# Opto.net
KiCad netlist of a schematic drawn in EAGLE
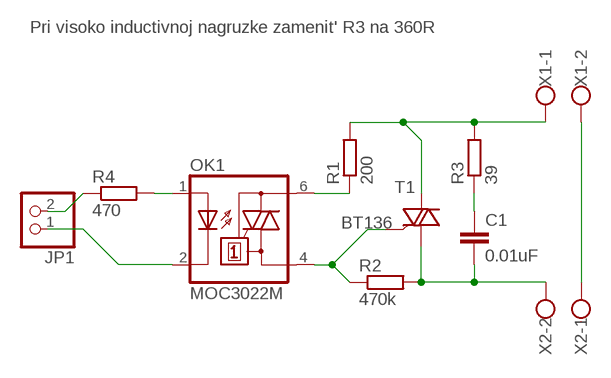
[diagram p0: schematic, sheet 1]

(export (version "E")
  (design (tool "Eeschema 10.0.6"))
  (components
    (comp (ref "C1")
      (value "0.01uF")
      (footprint "eagle-import:C102-043X133")
      (libsource (lib "eagle-import") (part "C-EU102-043X133"))
    )
    (comp (ref "JP1")
      (value "PINHD-1X2/90")
      (footprint "eagle-import:1X02_90")
      (libsource (lib "eagle-import") (part "PINHD-1X2/90"))
    )
    (comp (ref "OK1")
      (value "MOC3022M")
      (footprint "eagle-import:DIL06")
      (fields (field (name "MF") "FAIRCHILD SEMICONDUCTOR") (field (name "MPN") "MOC3022-M"))
      (libsource (lib "eagle-import") (part "MOC30M22"))
    )
    (comp (ref "R1")
      (value "200")
      (footprint "eagle-import:0207_2V")
      (libsource (lib "eagle-import") (part "R-EU_0207/2V"))
    )
    (comp (ref "R2")
      (value "470k")
      (footprint "eagle-import:0207_2V")
      (libsource (lib "eagle-import") (part "R-EU_0207/2V"))
    )
    (comp (ref "R3")
      (value "39")
      (footprint "eagle-import:0207_2V")
      (libsource (lib "eagle-import") (part "R-EU_0207/2V"))
    )
    (comp (ref "R4")
      (value "470")
      (footprint "eagle-import:R0805")
      (libsource (lib "eagle-import") (part "R-EU_R0805"))
    )
    (comp (ref "T1")
      (value "BT136")
      (footprint "eagle-import:TO220AB")
      (libsource (lib "eagle-import") (part "BT136"))
    )
    (comp (ref "X1")
      (value "W237-102")
      (footprint "eagle-import:W237-102")
      (fields (field (name "MPN") "237-102"))
      (libsource (lib "eagle-import") (part "W237-102"))
    )
    (comp (ref "X2")
      (value "W237-102")
      (footprint "eagle-import:W237-102")
      (fields (field (name "MPN") "237-102"))
      (libsource (lib "eagle-import") (part "W237-102"))
    )
  )
  (nets
    (net (code "1") (name "Net-(C1-Pad1)") (class "Default")
      (node (ref "C1") (pin "1") (pinfunction "1_1") (pintype "passive"))
      (node (ref "R3") (pin "1") (pinfunction "1_1") (pintype "passive"))
    )
    (net (code "2") (name "Net-(JP1-Pad2)") (class "Default")
      (node (ref "JP1") (pin "2") (pinfunction "2_2") (pintype "passive"))
      (node (ref "R4") (pin "1") (pinfunction "1_1") (pintype "passive"))
    )
    (net (code "3") (name "Net-(OK1-A)") (class "Default")
      (node (ref "OK1") (pin "1") (pinfunction "A_1") (pintype "passive"))
      (node (ref "R4") (pin "2") (pinfunction "2_2") (pintype "passive"))
    )
    (net (code "4") (name "Net-(OK1-A1)") (class "Default")
      (node (ref "OK1") (pin "4") (pinfunction "A1_4") (pintype "passive"))
      (node (ref "R2") (pin "1") (pinfunction "1_1") (pintype "passive"))
      (node (ref "T1") (pin "3") (pinfunction "G_3") (pintype "passive"))
    )
    (net (code "5") (name "Net-(OK1-A2)") (class "Default")
      (node (ref "OK1") (pin "6") (pinfunction "A2_6") (pintype "passive"))
      (node (ref "R1") (pin "1") (pinfunction "1_1") (pintype "passive"))
    )
    (net (code "6") (name "Net-(OK1-C)") (class "Default")
      (node (ref "JP1") (pin "1") (pinfunction "1_1") (pintype "passive"))
      (node (ref "OK1") (pin "2") (pinfunction "C_2") (pintype "passive"))
    )
    (net (code "7") (name "Net-(T1-A1)") (class "Default")
      (node (ref "C1") (pin "2") (pinfunction "2_2") (pintype "passive"))
      (node (ref "R2") (pin "2") (pinfunction "2_2") (pintype "passive"))
      (node (ref "T1") (pin "1") (pinfunction "A1_1") (pintype "passive"))
      (node (ref "X2") (pin "2") (pinfunction "KL_2") (pintype "passive"))
    )
    (net (code "8") (name "Net-(T1-A2)") (class "Default")
      (node (ref "R1") (pin "2") (pinfunction "2_2") (pintype "passive"))
      (node (ref "R3") (pin "2") (pinfunction "2_2") (pintype "passive"))
      (node (ref "T1") (pin "2") (pinfunction "A2_2") (pintype "passive"))
      (node (ref "X1") (pin "1") (pinfunction "KL_1") (pintype "passive"))
    )
    (net (code "9") (name "Net-(X1B-KL)") (class "Default")
      (node (ref "X1") (pin "2") (pinfunction "KL_2") (pintype "passive"))
      (node (ref "X2") (pin "1") (pinfunction "KL_1") (pintype "passive"))
    )
  )
)
